# Bottom_board.net
KiCad netlist of a schematic drawn in Altium Designer
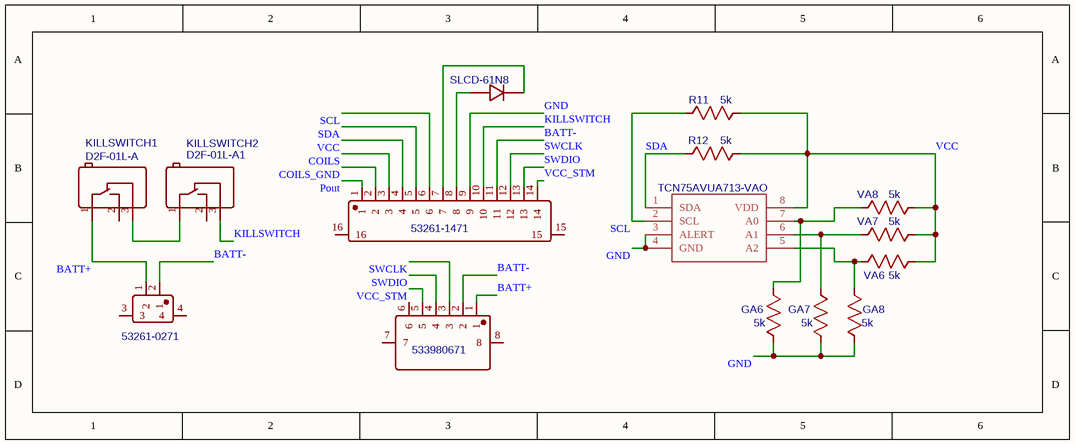
[diagram p0: Bottom_board.schdoc]

(export (version "E")
  (design (tool "Eeschema 10.0.6"))
  (components
    (comp (ref "CN1")
      (value "53261-0271")
      (footprint "CONN-SMD_532610271")
      (fields
        (field (name "BOM_SUPPLIER PART") "C189700")
        (field (name "BOM_MANUFACTURER PART") "532610271")
        (field (name "CONTRIBUTOR") "LCSC")
      )
      (libsource (lib "altium-import") (part "root_3_53261-0271_"))
    )
    (comp (ref "CN2")
      (value "53261-1471")
      (footprint "CONN-SMD_532611471")
      (fields
        (field (name "BOM_SUPPLIER PART") "C505101")
        (field (name "BOM_MANUFACTURER PART") "532611471")
        (field (name "CONTRIBUTOR") "LCSC")
      )
      (libsource (lib "altium-import") (part "root_3_53261-1471_"))
    )
    (comp (ref "D8")
      (value "SLCD-61N8")
      (footprint "SOD-123_L2.8-W1.8-LS3.7-RD")
      (fields
        (field (name "BOM_SUPPLIER PART") "C328592")
        (field (name "BOM_MANUFACTURER PART") "1N4007W")
        (field (name "CONTRIBUTOR") "Blothr")
      )
      (libsource (lib "altium-import") (part "root_0_SLCD-61N8_"))
    )
    (comp (ref "GA6")
      (value "5k")
      (footprint "R0805")
      (fields
        (field (name "BOM_SUPPLIER PART") "71-CRCW0805J-5K")
        (field (name "BOM_MANUFACTURER PART") "CRCW08055K00JNTA")
        (field (name "CONTRIBUTOR") "LCEDA_Lib")
      )
      (libsource (lib "altium-import") (part "root_1_5k_"))
    )
    (comp (ref "GA7")
      (value "5k")
      (footprint "R0805")
      (fields
        (field (name "BOM_SUPPLIER PART") "71-CRCW0805J-5K")
        (field (name "BOM_MANUFACTURER PART") "CRCW08055K00JNTA")
        (field (name "CONTRIBUTOR") "LCEDA_Lib")
      )
      (libsource (lib "altium-import") (part "root_1_5k_"))
    )
    (comp (ref "GA8")
      (value "5k")
      (footprint "R0805")
      (fields
        (field (name "BOM_SUPPLIER PART") "71-CRCW0805J-5K")
        (field (name "BOM_MANUFACTURER PART") "CRCW08055K00JNTA")
        (field (name "CONTRIBUTOR") "LCEDA_Lib")
      )
      (libsource (lib "altium-import") (part "root_1_5k_"))
    )
    (comp (ref "IC3")
      (value "TCN75AVUA713-VAO")
      (footprint "SOP65P490X110-8N")
      (libsource (lib "altium-import") (part "root_0_TCN75AVUA713-VAO_"))
    )
    (comp (ref "KILLSWITCH1")
      (value "D2F-01L-A")
      (footprint "SW-TH_D2F-01L")
      (fields
        (field (name "BOM_SUPPLIER PART") "C231335")
        (field (name "BOM_MANUFACTURER PART") "D2F-01L")
        (field (name "CONTRIBUTOR") "LCSC")
      )
      (libsource (lib "altium-import") (part "root_0_D2F-01L-A_"))
    )
    (comp (ref "KILLSWITCH2")
      (value "D2F-01L-A1")
      (footprint "SW-TH_D2F-01L")
      (fields
        (field (name "BOM_SUPPLIER PART") "C231335")
        (field (name "BOM_MANUFACTURER PART") "D2F-01L")
        (field (name "CONTRIBUTOR") "LCSC")
      )
      (libsource (lib "altium-import") (part "root_0_D2F-01L-A1_"))
    )
    (comp (ref "R11")
      (value "5k")
      (footprint "R0805")
      (fields
        (field (name "BOM_SUPPLIER PART") "71-CRCW0805J-5K")
        (field (name "BOM_MANUFACTURER PART") "CRCW08055K00JNTA")
        (field (name "CONTRIBUTOR") "LCEDA_Lib")
      )
      (libsource (lib "altium-import") (part "root_0_5k_"))
    )
    (comp (ref "R12")
      (value "5k")
      (footprint "R0805")
      (fields
        (field (name "BOM_SUPPLIER PART") "71-CRCW0805J-5K")
        (field (name "BOM_MANUFACTURER PART") "CRCW08055K00JNTA")
        (field (name "CONTRIBUTOR") "LCEDA_Lib")
      )
      (libsource (lib "altium-import") (part "root_0_5k_"))
    )
    (comp (ref "U8")
      (value "533980671")
      (footprint "CONN-SMD_6P-P1.25-V-M_533980671")
      (fields (field (name "BOM_SUPPLIER PART") "C277393") (field (name "CONTRIBUTOR") "LCSC"))
      (libsource (lib "altium-import") (part "root_3_533980671_"))
    )
    (comp (ref "VA6")
      (value "5k")
      (footprint "R0805")
      (fields
        (field (name "BOM_SUPPLIER PART") "71-CRCW0805J-5K")
        (field (name "BOM_MANUFACTURER PART") "CRCW08055K00JNTA")
        (field (name "CONTRIBUTOR") "LCEDA_Lib")
      )
      (libsource (lib "altium-import") (part "root_0_5k_"))
    )
    (comp (ref "VA7")
      (value "5k")
      (footprint "R0805")
      (fields
        (field (name "BOM_SUPPLIER PART") "71-CRCW0805J-5K")
        (field (name "BOM_MANUFACTURER PART") "CRCW08055K00JNTA")
        (field (name "CONTRIBUTOR") "LCEDA_Lib")
      )
      (libsource (lib "altium-import") (part "root_0_5k_"))
    )
    (comp (ref "VA8")
      (value "5k")
      (footprint "R0805")
      (fields
        (field (name "BOM_SUPPLIER PART") "71-CRCW0805J-5K")
        (field (name "BOM_MANUFACTURER PART") "CRCW08055K00JNTA")
        (field (name "CONTRIBUTOR") "LCEDA_Lib")
      )
      (libsource (lib "altium-import") (part "root_0_5k_"))
    )
  )
  (nets
    (net (code "1") (name "/BATT+") (class "Default")
      (node (ref "CN1") (pin "1") (pinfunction "2_1") (pintype "passive"))
      (node (ref "KILLSWITCH1") (pin "1") (pinfunction "COM_1") (pintype "passive"))
      (node (ref "U8") (pin "1") (pinfunction "1_1") (pintype "passive"))
    )
    (net (code "2") (name "/BATT-") (class "Default")
      (node (ref "CN1") (pin "2") (pinfunction "1_2") (pintype "passive"))
      (node (ref "CN2") (pin "11") (pinfunction "11_11") (pintype "passive"))
      (node (ref "U8") (pin "2") (pinfunction "2_2") (pintype "passive"))
    )
    (net (code "3") (name "/COILS") (class "Default")
      (node (ref "CN2") (pin "3") (pinfunction "3_3") (pintype "passive"))
    )
    (net (code "4") (name "/COILS_GND") (class "Default")
      (node (ref "CN2") (pin "2") (pinfunction "2_2") (pintype "passive"))
    )
    (net (code "5") (name "/GND") (class "Default")
      (node (ref "CN2") (pin "9") (pinfunction "9_9") (pintype "passive"))
      (node (ref "GA6") (pin "1") (pinfunction "1_1") (pintype "passive"))
      (node (ref "GA7") (pin "1") (pinfunction "1_1") (pintype "passive"))
      (node (ref "GA8") (pin "1") (pinfunction "1_1") (pintype "passive"))
      (node (ref "IC3") (pin "3") (pinfunction "ALERT_3") (pintype "passive"))
      (node (ref "IC3") (pin "4") (pinfunction "GND_4") (pintype "passive"))
    )
    (net (code "6") (name "/KILLSWITCH") (class "Default")
      (node (ref "CN2") (pin "10") (pinfunction "10_10") (pintype "passive"))
      (node (ref "KILLSWITCH2") (pin "3") (pinfunction "NC_3") (pintype "passive"))
    )
    (net (code "7") (name "/Pout") (class "Default")
      (node (ref "CN2") (pin "1") (pinfunction "1_1") (pintype "passive"))
    )
    (net (code "8") (name "/SCL") (class "Default")
      (node (ref "CN2") (pin "6") (pinfunction "6_6") (pintype "passive"))
      (node (ref "IC3") (pin "2") (pinfunction "SCL_2") (pintype "passive"))
      (node (ref "R11") (pin "1") (pinfunction "1_1") (pintype "passive"))
    )
    (net (code "9") (name "/SDA") (class "Default")
      (node (ref "CN2") (pin "5") (pinfunction "5_5") (pintype "passive"))
      (node (ref "IC3") (pin "1") (pinfunction "SDA_1") (pintype "passive"))
      (node (ref "R12") (pin "1") (pinfunction "1_1") (pintype "passive"))
    )
    (net (code "10") (name "/SWCLK") (class "Default")
      (node (ref "CN2") (pin "12") (pinfunction "12_12") (pintype "passive"))
      (node (ref "U8") (pin "3") (pinfunction "3_3") (pintype "passive"))
    )
    (net (code "11") (name "/SWDIO") (class "Default")
      (node (ref "CN2") (pin "13") (pinfunction "13_13") (pintype "passive"))
      (node (ref "U8") (pin "4") (pinfunction "4_4") (pintype "passive"))
    )
    (net (code "12") (name "/VCC") (class "Default")
      (node (ref "CN2") (pin "4") (pinfunction "4_4") (pintype "passive"))
      (node (ref "IC3") (pin "8") (pinfunction "VDD_8") (pintype "passive"))
      (node (ref "R11") (pin "2") (pinfunction "2_2") (pintype "passive"))
      (node (ref "R12") (pin "2") (pinfunction "2_2") (pintype "passive"))
      (node (ref "VA6") (pin "2") (pinfunction "2_2") (pintype "passive"))
      (node (ref "VA7") (pin "2") (pinfunction "2_2") (pintype "passive"))
      (node (ref "VA8") (pin "2") (pinfunction "2_2") (pintype "passive"))
    )
    (net (code "13") (name "/VCC_STM") (class "Default")
      (node (ref "CN2") (pin "14") (pinfunction "14_14") (pintype "passive"))
      (node (ref "U8") (pin "5") (pinfunction "5_5") (pintype "passive"))
    )
    (net (code "14") (name "Net-(CN2-Pad7)") (class "Default")
      (node (ref "CN2") (pin "7") (pinfunction "7_7") (pintype "passive"))
      (node (ref "D8") (pin "1") (pinfunction "1_1") (pintype "passive"))
    )
    (net (code "15") (name "Net-(CN2-Pad8)") (class "Default")
      (node (ref "CN2") (pin "8") (pinfunction "8_8") (pintype "passive"))
      (node (ref "D8") (pin "2") (pinfunction "2_2") (pintype "passive"))
    )
    (net (code "16") (name "Net-(IC3-A0)") (class "Default")
      (node (ref "GA6") (pin "2") (pinfunction "2_2") (pintype "passive"))
      (node (ref "IC3") (pin "7") (pinfunction "A0_7") (pintype "passive"))
      (node (ref "VA8") (pin "1") (pinfunction "1_1") (pintype "passive"))
    )
    (net (code "17") (name "Net-(IC3-A1)") (class "Default")
      (node (ref "GA7") (pin "2") (pinfunction "2_2") (pintype "passive"))
      (node (ref "IC3") (pin "6") (pinfunction "A1_6") (pintype "passive"))
      (node (ref "VA7") (pin "1") (pinfunction "1_1") (pintype "passive"))
    )
    (net (code "18") (name "Net-(IC3-A2)") (class "Default")
      (node (ref "GA8") (pin "2") (pinfunction "2_2") (pintype "passive"))
      (node (ref "IC3") (pin "5") (pinfunction "A2_5") (pintype "passive"))
      (node (ref "VA6") (pin "1") (pinfunction "1_1") (pintype "passive"))
    )
    (net (code "19") (name "Net-(KILLSWITCH1-NC)") (class "Default")
      (node (ref "KILLSWITCH1") (pin "3") (pinfunction "NC_3") (pintype "passive"))
      (node (ref "KILLSWITCH2") (pin "1") (pinfunction "COM_1") (pintype "passive"))
    )
    (net (code "20") (name "unconnected-(CN1-Pad3)") (class "Default")
      (node (ref "CN1") (pin "3") (pinfunction "3_3") (pintype "passive"))
    )
    (net (code "21") (name "unconnected-(CN1-Pad4)") (class "Default")
      (node (ref "CN1") (pin "4") (pinfunction "4_4") (pintype "passive"))
    )
    (net (code "22") (name "unconnected-(CN2-Pad15)") (class "Default")
      (node (ref "CN2") (pin "15") (pinfunction "15_15") (pintype "passive"))
    )
    (net (code "23") (name "unconnected-(CN2-Pad16)") (class "Default")
      (node (ref "CN2") (pin "16") (pinfunction "16_16") (pintype "passive"))
    )
    (net (code "24") (name "unconnected-(KILLSWITCH1-NO-Pad2)") (class "Default")
      (node (ref "KILLSWITCH1") (pin "2") (pinfunction "NO_2") (pintype "passive"))
    )
    (net (code "25") (name "unconnected-(KILLSWITCH2-NO-Pad2)") (class "Default")
      (node (ref "KILLSWITCH2") (pin "2") (pinfunction "NO_2") (pintype "passive"))
    )
    (net (code "26") (name "unconnected-(U8-Pad6)") (class "Default")
      (node (ref "U8") (pin "6") (pinfunction "6_6") (pintype "passive"))
    )
    (net (code "27") (name "unconnected-(U8-Pad7)") (class "Default")
      (node (ref "U8") (pin "7") (pinfunction "7_7") (pintype "passive"))
    )
    (net (code "28") (name "unconnected-(U8-Pad8)") (class "Default")
      (node (ref "U8") (pin "8") (pinfunction "8_8") (pintype "passive"))
    )
  )
)
